# pedometer.net
KiCad netlist of a schematic drawn in EAGLE
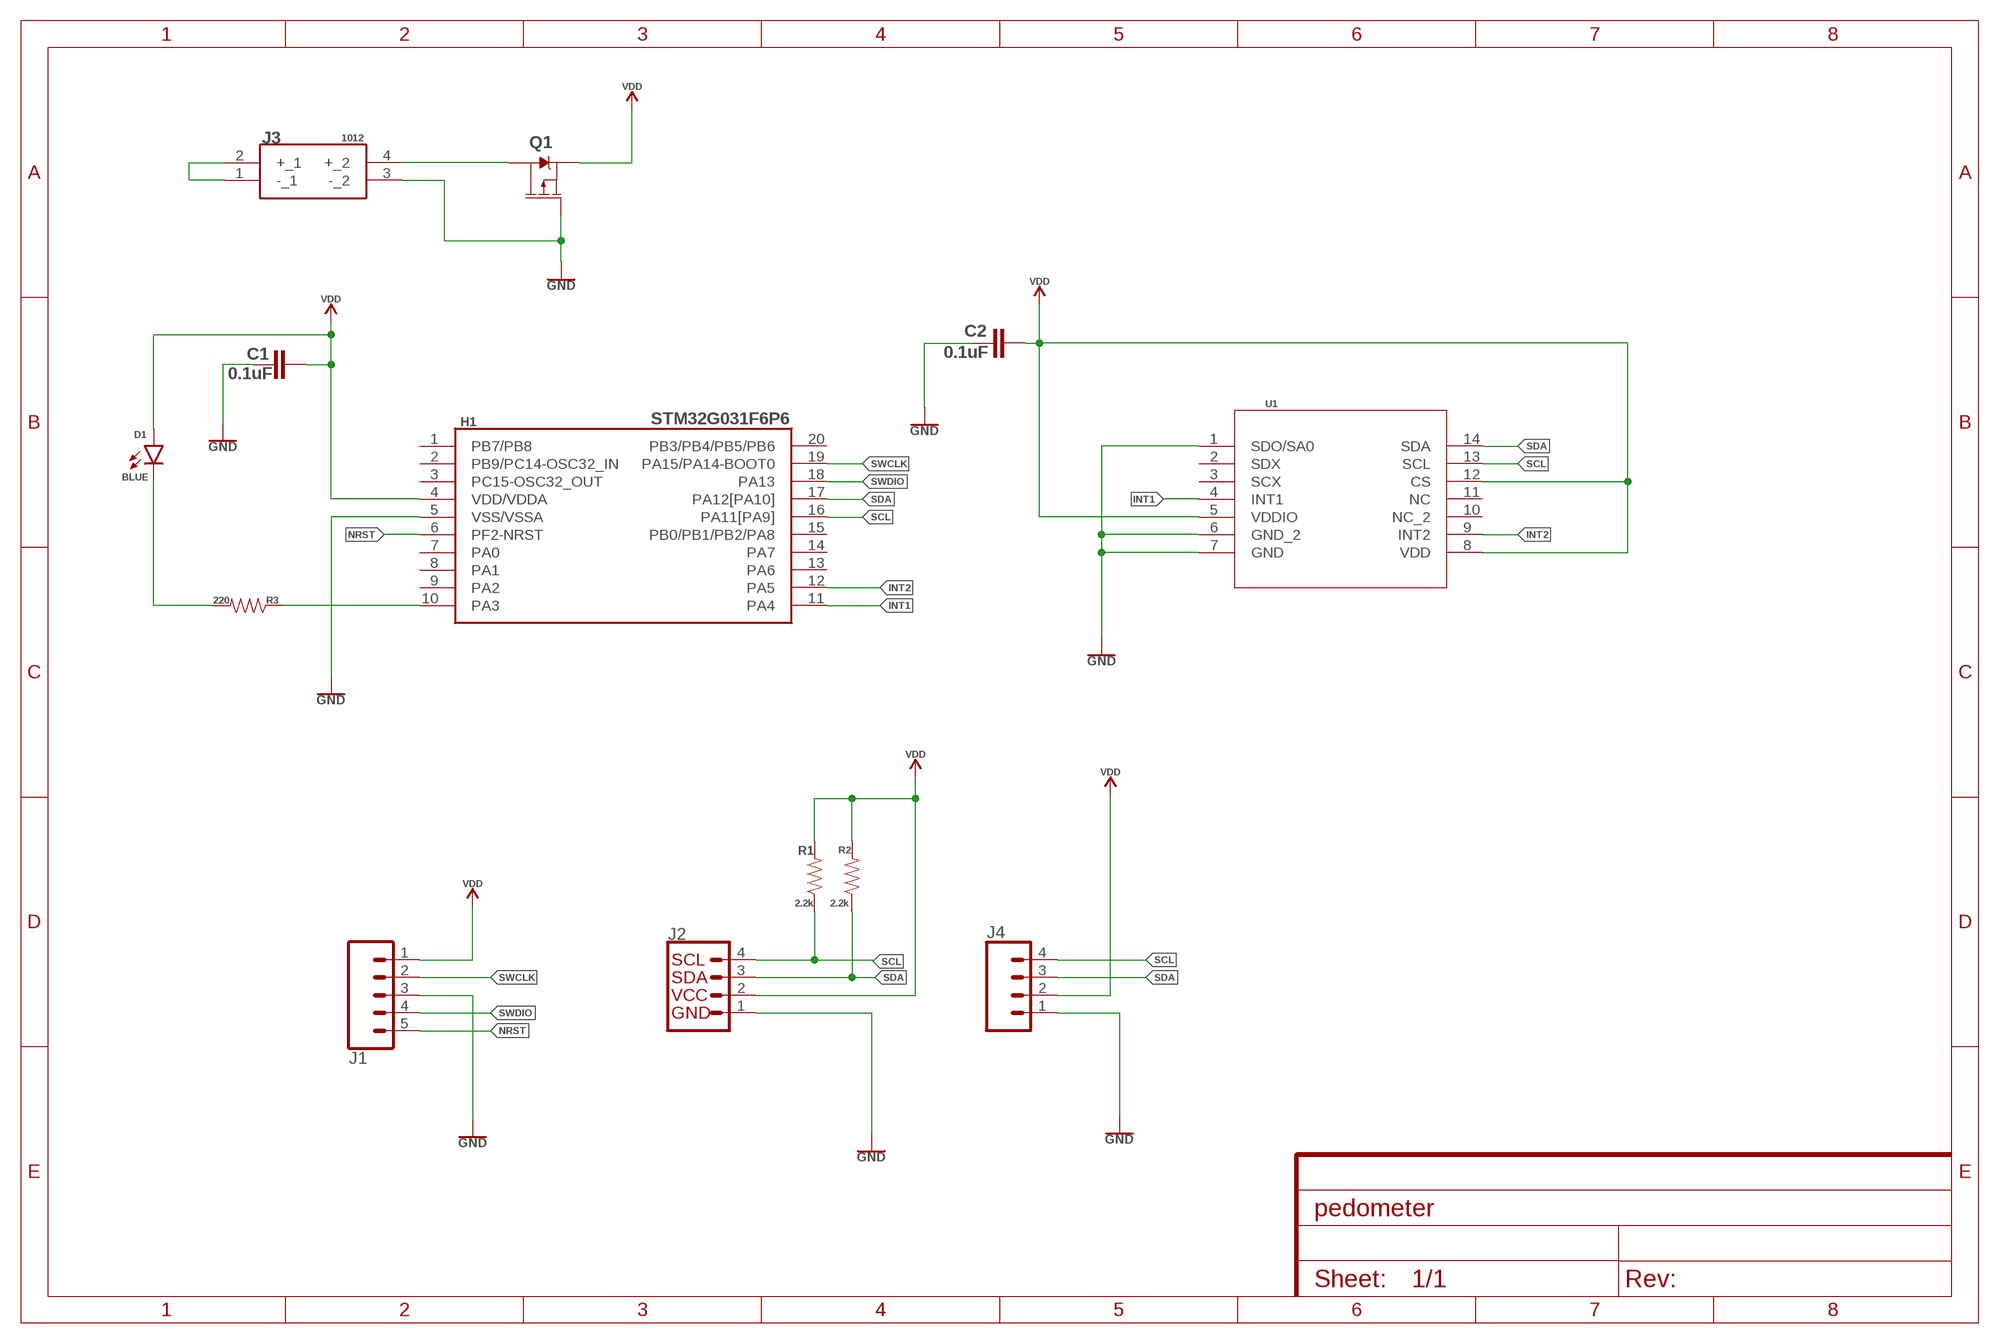
[diagram p0: schematic, sheet 1]

(export (version "E")
  (design (tool "Eeschema 10.0.6"))
  (components
    (comp (ref "C1")
      (value "0.1uF")
      (footprint "eagle-import:0603")
      (libsource (lib "eagle-import") (part "0.1UF-0603-25V-(+80/-20%)"))
    )
    (comp (ref "C2")
      (value "0.1uF")
      (footprint "eagle-import:0603")
      (libsource (lib "eagle-import") (part "0.1UF-0603-25V-(+80/-20%)"))
    )
    (comp (ref "D1")
      (value "BLUE")
      (footprint "eagle-import:LED-0603")
      (libsource (lib "eagle-import") (part "LED-BLUE0603"))
    )
    (comp (ref "H1")
      (value "STM32G031F6P6")
      (footprint "eagle-import:SOP65P640X120-20N")
      (fields (field (name "MOUSER_PART_NUMBER") "511-STM32G031F6P6"))
      (libsource (lib "eagle-import") (part "STM32G031F6P6"))
    )
    (comp (ref "J1")
      (value "CONN_05")
      (footprint "eagle-import:1X05")
      (libsource (lib "eagle-import") (part "CONN_05"))
    )
    (comp (ref "J2")
      (value "QWIIC_CONNECTORJS-1MM")
      (footprint "eagle-import:1X04_1MM_RA")
      (libsource (lib "eagle-import") (part "QWIIC_CONNECTORJS-1MM"))
    )
    (comp (ref "J3")
      (value "1012")
      (footprint "eagle-import:1012")
      (fields (field (name "MF") "Keystone Electronics"))
      (libsource (lib "eagle-import") (part "1012"))
    )
    (comp (ref "J4")
      (value "CONN_04")
      (footprint "eagle-import:1X04")
      (libsource (lib "eagle-import") (part "CONN_04"))
    )
    (comp (ref "Q1")
      (value "2.5A/30V/105mΩ")
      (footprint "eagle-import:SOT23-3")
      (libsource (lib "eagle-import") (part "MOSFET_PCH-DMG2307L"))
    )
    (comp (ref "R1")
      (value "2.2k")
      (footprint "eagle-import:0603")
      (libsource (lib "eagle-import") (part "2.2KOHM-0603-1/10W-1%"))
    )
    (comp (ref "R2")
      (value "2.2k")
      (footprint "eagle-import:0603")
      (libsource (lib "eagle-import") (part "2.2KOHM-0603-1/10W-1%"))
    )
    (comp (ref "R3")
      (value "220")
      (footprint "eagle-import:0603")
      (libsource (lib "eagle-import") (part "220OHM-0603-1/10W-1%"))
    )
    (comp (ref "U1")
      (value "LSM6DSO32TRLGA-14L_2P5X3X0P83_STM-M")
      (footprint "eagle-import:LGA-14L_2P5X3X0P83_STM-M")
      (fields
        (field (name "MANUFACTURER_PART_NUMBER") "LSM6DSO32TR")
        (field (name "COPYRIGHT") "Copyright (C) 2022 Ultra Librarian. All rights reserved.")
      )
      (libsource (lib "eagle-import") (part "LSM6DSO32TRLGA-14L_2P5X3X0P83_STM-M"))
    )
  )
  (nets
    (net (code "1") (name "GND") (class "Default")
      (node (ref "C1") (pin "1") (pinfunction "1_1") (pintype "passive"))
      (node (ref "C2") (pin "1") (pinfunction "1_1") (pintype "passive"))
      (node (ref "H1") (pin "5") (pinfunction "VSS/VSSA_5") (pintype "power_in"))
      (node (ref "J1") (pin "3") (pinfunction "3_3") (pintype "passive"))
      (node (ref "J2") (pin "1") (pinfunction "1_1") (pintype "power_in"))
      (node (ref "J3") (pin "3") (pinfunction "-_2_3") (pintype "bidirectional"))
      (node (ref "J4") (pin "1") (pinfunction "VCC_1") (pintype "passive"))
      (node (ref "Q1") (pin "1") (pinfunction "G_1") (pintype "bidirectional"))
      (node (ref "U1") (pin "1") (pinfunction "SDO/SA0_1") (pintype "bidirectional"))
      (node (ref "U1") (pin "6") (pinfunction "GND_2_6") (pintype "passive"))
      (node (ref "U1") (pin "7") (pinfunction "GND_7") (pintype "passive"))
    )
    (net (code "2") (name "INT1") (class "Default")
      (node (ref "H1") (pin "11") (pinfunction "PA4_11") (pintype "bidirectional"))
      (node (ref "U1") (pin "4") (pinfunction "INT1_4") (pintype "output"))
    )
    (net (code "3") (name "INT2") (class "Default")
      (node (ref "H1") (pin "12") (pinfunction "PA5_12") (pintype "bidirectional"))
      (node (ref "U1") (pin "9") (pinfunction "INT2_9") (pintype "output"))
    )
    (net (code "4") (name "NRST") (class "Default")
      (node (ref "H1") (pin "6") (pinfunction "PF2-NRST_6") (pintype "bidirectional"))
      (node (ref "J1") (pin "5") (pinfunction "5_5") (pintype "passive"))
    )
    (net (code "5") (name "Net-(D1-PadC)") (class "Default")
      (node (ref "D1") (pin "C") (pinfunction "C_C") (pintype "passive"))
      (node (ref "R3") (pin "2") (pinfunction "2_2") (pintype "passive"))
    )
    (net (code "6") (name "Net-(H1-PA3)") (class "Default")
      (node (ref "H1") (pin "10") (pinfunction "PA3_10") (pintype "bidirectional"))
      (node (ref "R3") (pin "1") (pinfunction "1_1") (pintype "passive"))
    )
    (net (code "7") (name "Net-(J3-+_1)") (class "Default")
      (node (ref "J3") (pin "1") (pinfunction "-_1_1") (pintype "bidirectional"))
      (node (ref "J3") (pin "2") (pinfunction "+_1_2") (pintype "bidirectional"))
    )
    (net (code "8") (name "Net-(J3-+_2)") (class "Default")
      (node (ref "J3") (pin "4") (pinfunction "+_2_4") (pintype "bidirectional"))
      (node (ref "Q1") (pin "3") (pinfunction "D_3") (pintype "bidirectional"))
    )
    (net (code "9") (name "SCL") (class "Default")
      (node (ref "H1") (pin "16") (pinfunction "PA11[PA9]_16") (pintype "bidirectional"))
      (node (ref "J2") (pin "4") (pinfunction "4_4") (pintype "passive"))
      (node (ref "J4") (pin "4") (pinfunction "GND_4") (pintype "passive"))
      (node (ref "R1") (pin "1") (pinfunction "1_1") (pintype "passive"))
      (node (ref "U1") (pin "13") (pinfunction "SCL_13") (pintype "input"))
    )
    (net (code "10") (name "SDA") (class "Default")
      (node (ref "H1") (pin "17") (pinfunction "PA12[PA10]_17") (pintype "bidirectional"))
      (node (ref "J2") (pin "3") (pinfunction "3_3") (pintype "passive"))
      (node (ref "J4") (pin "3") (pinfunction "SDA_3") (pintype "passive"))
      (node (ref "R2") (pin "1") (pinfunction "1_1") (pintype "passive"))
      (node (ref "U1") (pin "14") (pinfunction "SDA_14") (pintype "bidirectional"))
    )
    (net (code "11") (name "SWCLK") (class "Default")
      (node (ref "H1") (pin "19") (pinfunction "PA15/PA14-BOOT0_19") (pintype "bidirectional"))
      (node (ref "J1") (pin "2") (pinfunction "2_2") (pintype "passive"))
    )
    (net (code "12") (name "SWDIO") (class "Default")
      (node (ref "H1") (pin "18") (pinfunction "PA13_18") (pintype "bidirectional"))
      (node (ref "J1") (pin "4") (pinfunction "4_4") (pintype "passive"))
    )
    (net (code "13") (name "VDD") (class "Default")
      (node (ref "C1") (pin "2") (pinfunction "2_2") (pintype "passive"))
      (node (ref "C2") (pin "2") (pinfunction "2_2") (pintype "passive"))
      (node (ref "D1") (pin "A") (pinfunction "A_A") (pintype "passive"))
      (node (ref "H1") (pin "4") (pinfunction "VDD/VDDA_4") (pintype "power_in"))
      (node (ref "J1") (pin "1") (pinfunction "1_1") (pintype "passive"))
      (node (ref "J2") (pin "2") (pinfunction "2_2") (pintype "power_in"))
      (node (ref "J4") (pin "2") (pinfunction "SCL_2") (pintype "passive"))
      (node (ref "Q1") (pin "2") (pinfunction "S_2") (pintype "bidirectional"))
      (node (ref "R1") (pin "2") (pinfunction "2_2") (pintype "passive"))
      (node (ref "R2") (pin "2") (pinfunction "2_2") (pintype "passive"))
      (node (ref "U1") (pin "12") (pinfunction "CS_12") (pintype "input"))
      (node (ref "U1") (pin "5") (pinfunction "VDDIO_5") (pintype "power_in"))
      (node (ref "U1") (pin "8") (pinfunction "VDD_8") (pintype "power_in"))
    )
    (net (code "14") (name "unconnected-(H1-PA0-Pad7)") (class "Default")
      (node (ref "H1") (pin "7") (pinfunction "PA0_7") (pintype "bidirectional"))
    )
    (net (code "15") (name "unconnected-(H1-PA1-Pad8)") (class "Default")
      (node (ref "H1") (pin "8") (pinfunction "PA1_8") (pintype "bidirectional"))
    )
    (net (code "16") (name "unconnected-(H1-PA2-Pad9)") (class "Default")
      (node (ref "H1") (pin "9") (pinfunction "PA2_9") (pintype "bidirectional"))
    )
    (net (code "17") (name "unconnected-(H1-PA6-Pad13)") (class "Default")
      (node (ref "H1") (pin "13") (pinfunction "PA6_13") (pintype "bidirectional"))
    )
    (net (code "18") (name "unconnected-(H1-PA7-Pad14)") (class "Default")
      (node (ref "H1") (pin "14") (pinfunction "PA7_14") (pintype "bidirectional"))
    )
    (net (code "19") (name "unconnected-(H1-PB0{slash}PB1{slash}PB2{slash}PA8-Pad15)") (class "Default")
      (node (ref "H1") (pin "15") (pinfunction "PB0/PB1/PB2/PA8_15") (pintype "bidirectional"))
    )
    (net (code "20") (name "unconnected-(H1-PB3{slash}PB4{slash}PB5{slash}PB6-Pad20)") (class "Default")
      (node (ref "H1") (pin "20") (pinfunction "PB3/PB4/PB5/PB6_20") (pintype "bidirectional"))
    )
    (net (code "21") (name "unconnected-(H1-PB7{slash}PB8-Pad1)") (class "Default")
      (node (ref "H1") (pin "1") (pinfunction "PB7/PB8_1") (pintype "bidirectional"))
    )
    (net (code "22") (name "unconnected-(H1-PB9{slash}PC14-OSC32_IN-Pad2)") (class "Default")
      (node (ref "H1") (pin "2") (pinfunction "PB9/PC14-OSC32_IN_2") (pintype "bidirectional"))
    )
    (net (code "23") (name "unconnected-(H1-PC15-OSC32_OUT-Pad3)") (class "Default")
      (node (ref "H1") (pin "3") (pinfunction "PC15-OSC32_OUT_3") (pintype "bidirectional"))
    )
    (net (code "24") (name "unconnected-(U1-NC-Pad11)") (class "Default")
      (node (ref "U1") (pin "11") (pinfunction "NC_11") (pintype "no_connect"))
    )
    (net (code "25") (name "unconnected-(U1-NC_2-Pad10)") (class "Default")
      (node (ref "U1") (pin "10") (pinfunction "NC_2_10") (pintype "no_connect"))
    )
    (net (code "26") (name "unconnected-(U1-SCX-Pad3)") (class "Default")
      (node (ref "U1") (pin "3") (pinfunction "SCX_3") (pintype "passive"))
    )
    (net (code "27") (name "unconnected-(U1-SDX-Pad2)") (class "Default")
      (node (ref "U1") (pin "2") (pinfunction "SDX_2") (pintype "passive"))
    )
  )
)
